# Core.net
KiCad netlist of a schematic drawn in Altium Designer
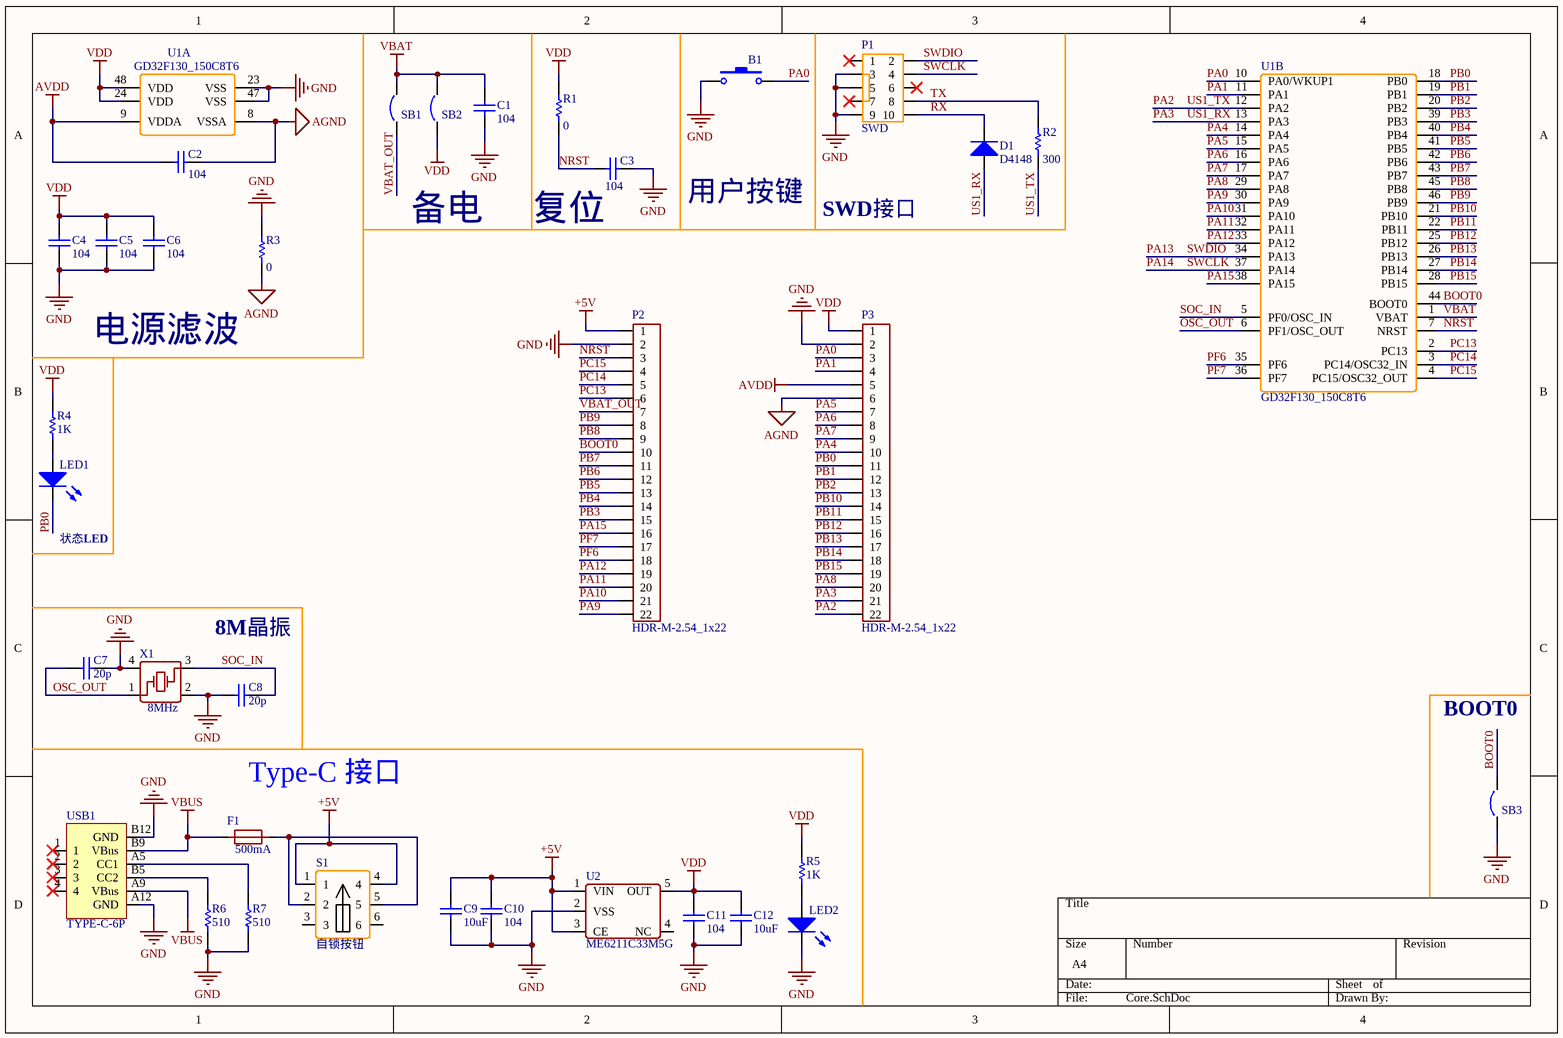
[diagram p0: Core.SchDoc]

(export (version "E")
  (design (tool "Eeschema 10.0.6"))
  (components
    (comp (ref "B1")
      (value "Button")
      (footprint "SW-SMD_L6.0-W3.5-LS8.0")
      (description "轻触按钮 - Switch")
      (fields (field (name "PUBLISHER") "Altium Limited"))
      (libsource (lib "ZSF-90") (part "Button"))
    )
    (comp (ref "C1")
      (value "104")
      (footprint "C0402")
      (description "无极性电容")
      (fields (field (name "Comment") "Cap") (field (name "PUBLISHER") "信念D力量"))
      (libsource (lib "ZSF-90") (part "Cap"))
    )
    (comp (ref "C2")
      (value "104")
      (footprint "C0402")
      (description "无极性电容")
      (fields (field (name "Comment") "Cap") (field (name "PUBLISHER") "信念D力量"))
      (libsource (lib "ZSF-90") (part "Cap"))
    )
    (comp (ref "C3")
      (value "104")
      (footprint "C0402")
      (description "无极性电容")
      (fields (field (name "Comment") "Cap") (field (name "PUBLISHER") "信念D力量"))
      (libsource (lib "ZSF-90") (part "Cap"))
    )
    (comp (ref "C4")
      (value "104")
      (footprint "C0402")
      (description "无极性电容")
      (fields (field (name "Comment") "Cap") (field (name "PUBLISHER") "信念D力量"))
      (libsource (lib "ZSF-90") (part "Cap"))
    )
    (comp (ref "C5")
      (value "104")
      (footprint "C0402")
      (description "无极性电容")
      (fields (field (name "Comment") "Cap") (field (name "PUBLISHER") "信念D力量"))
      (libsource (lib "ZSF-90") (part "Cap"))
    )
    (comp (ref "C6")
      (value "104")
      (footprint "C0402")
      (description "无极性电容")
      (fields (field (name "Comment") "Cap") (field (name "PUBLISHER") "信念D力量"))
      (libsource (lib "ZSF-90") (part "Cap"))
    )
    (comp (ref "C7")
      (value "20p")
      (footprint "C0603")
      (description "无极性电容")
      (fields (field (name "Comment") "Cap") (field (name "PUBLISHER") "信念D力量"))
      (libsource (lib "ZSF-90") (part "Cap"))
    )
    (comp (ref "C8")
      (value "20p")
      (footprint "C0603")
      (description "无极性电容")
      (fields (field (name "Comment") "Cap") (field (name "PUBLISHER") "信念D力量"))
      (libsource (lib "ZSF-90") (part "Cap"))
    )
    (comp (ref "C9")
      (value "10uF")
      (footprint "C0603")
      (description "无极性电容")
      (fields (field (name "Comment") "Cap") (field (name "PUBLISHER") "信念D力量"))
      (libsource (lib "ZSF-90") (part "Cap"))
    )
    (comp (ref "C10")
      (value "104")
      (footprint "C0402")
      (description "无极性电容")
      (fields (field (name "Comment") "Cap") (field (name "PUBLISHER") "信念D力量"))
      (libsource (lib "ZSF-90") (part "Cap"))
    )
    (comp (ref "C11")
      (value "104")
      (footprint "C0402")
      (description "无极性电容")
      (fields (field (name "Comment") "Cap") (field (name "PUBLISHER") "信念D力量"))
      (libsource (lib "ZSF-90") (part "Cap"))
    )
    (comp (ref "C12")
      (value "10uF")
      (footprint "C0603")
      (description "无极性电容")
      (fields (field (name "Comment") "Cap") (field (name "PUBLISHER") "信念D力量"))
      (libsource (lib "ZSF-90") (part "Cap"))
    )
    (comp (ref "D1")
      (value "D4148")
      (footprint "SOD-80_L3.5-W1.5-RD")
      (description "4148二极管")
      (libsource (lib "ZSF-90") (part "D4148"))
    )
    (comp (ref "F1")
      (value "500mA")
      (footprint "F0603")
      (description "保险丝 - Fuse")
      (libsource (lib "ZSF-90") (part "Fuse 1"))
    )
    (comp (ref "LED1")
      (value "LED")
      (footprint "LED0603_RED")
      (description "发光二极管")
      (libsource (lib "ZSF-90") (part "LED"))
    )
    (comp (ref "LED2")
      (value "LED")
      (footprint "LED0603_RED")
      (description "发光二极管")
      (libsource (lib "ZSF-90") (part "LED"))
    )
    (comp (ref "P1")
      (value "SWD")
      (footprint "IDC-SMD-10P-1.27MM")
      (description "牛角座")
      (libsource (lib "ZSF-90") (part "IDC-2x5"))
    )
    (comp (ref "P2")
      (value "HDR-M-2.54_1x22")
      (footprint "HDR1X22-MALE")
      (description "排针，2.54MM")
      (libsource (lib "ZSF-90") (part "HDR-M-2.54_1x22"))
    )
    (comp (ref "P3")
      (value "HDR-M-2.54_1x22")
      (footprint "HDR1X22-MALE")
      (description "排针，2.54MM")
      (libsource (lib "ZSF-90") (part "HDR-M-2.54_1x22"))
    )
    (comp (ref "R1")
      (value "0")
      (footprint "R0402")
      (description "美国电阻符号")
      (fields (field (name "Comment") "Res") (field (name "PUBLISHER") "Altium Limited"))
      (libsource (lib "ZSF-90") (part "Res"))
    )
    (comp (ref "R2")
      (value "300")
      (footprint "R0402")
      (description "美国电阻符号")
      (fields (field (name "Comment") "Res") (field (name "PUBLISHER") "Altium Limited"))
      (libsource (lib "ZSF-90") (part "Res"))
    )
    (comp (ref "R3")
      (value "0")
      (footprint "R0402")
      (description "美国电阻符号")
      (fields (field (name "Comment") "Res") (field (name "PUBLISHER") "Altium Limited"))
      (libsource (lib "ZSF-90") (part "Res"))
    )
    (comp (ref "R4")
      (value "1K")
      (footprint "R0402")
      (description "美国电阻符号")
      (fields (field (name "Comment") "Res") (field (name "PUBLISHER") "Altium Limited"))
      (libsource (lib "ZSF-90") (part "Res"))
    )
    (comp (ref "R5")
      (value "1K")
      (footprint "R0402")
      (description "美国电阻符号")
      (fields (field (name "Comment") "Res") (field (name "PUBLISHER") "Altium Limited"))
      (libsource (lib "ZSF-90") (part "Res"))
    )
    (comp (ref "R6")
      (value "510")
      (footprint "R0402")
      (description "美国电阻符号")
      (fields (field (name "Comment") "Res") (field (name "PUBLISHER") "Altium Limited"))
      (libsource (lib "ZSF-90") (part "Res"))
    )
    (comp (ref "R7")
      (value "510")
      (footprint "R0402")
      (description "美国电阻符号")
      (fields (field (name "Comment") "Res") (field (name "PUBLISHER") "Altium Limited"))
      (libsource (lib "ZSF-90") (part "Res"))
    )
    (comp (ref "S1")
      (value "自锁按钮")
      (footprint "SW-TH_5.8ZSGT")
      (description "自锁按钮开个")
      (libsource (lib "ZSF90_Connector") (part "自锁按钮"))
    )
    (comp (ref "SB1")
      (value "Circuit Breaker")
      (footprint "JP2_SMD")
      (description "断路器 短路选择 - Circuit Breaker")
      (fields (field (name "PUBLISHER") "Altium Limited"))
      (libsource (lib "ZSF-90") (part "Circuit Breaker"))
    )
    (comp (ref "SB2")
      (value "Circuit Breaker")
      (footprint "JP2_SMD")
      (description "断路器 短路选择 - Circuit Breaker")
      (fields (field (name "PUBLISHER") "Altium Limited"))
      (libsource (lib "ZSF-90") (part "Circuit Breaker"))
    )
    (comp (ref "SB3")
      (value "Circuit Breaker")
      (footprint "JP2_SMD")
      (description "断路器 短路选择 - Circuit Breaker")
      (fields (field (name "PUBLISHER") "Altium Limited"))
      (libsource (lib "ZSF-90") (part "Circuit Breaker"))
    )
    (comp (ref "U1")
      (value "GD32F130_150C8T6")
      (footprint "LQFP48 7X7")
      (description "GD32 单片机")
      (libsource (lib "ZSF-90") (part "GD32F130_150C8T6"))
    )
    (comp (ref "U2")
      (value "ME6211C33M5G")
      (footprint "SOT-23-5L")
      (description "3.3V LDO 线性稳压，带使能控制")
      (libsource (lib "ZSF-90") (part "ME6211C33M5G"))
    )
    (comp (ref "USB1")
      (value "TYPE-C-6P")
      (footprint "USB-C-SMD_6P")
      (description "Type-C USB，6P")
      (libsource (lib "ZSF-90") (part "TYPE-C-6P"))
    )
    (comp (ref "X1")
      (value "8MHz")
      (footprint "SMD-5032")
      (description "4脚晶振")
      (libsource (lib "ZSF-90") (part "XTAL-4"))
    )
  )
  (nets
    (net (code "1") (name "+5V") (class "Default")
      (node (ref "C10") (pin "2") (pinfunction "2_2") (pintype "passive"))
      (node (ref "C9") (pin "2") (pinfunction "2_2") (pintype "passive"))
      (node (ref "P2") (pin "1") (pinfunction "1_1") (pintype "passive"))
      (node (ref "S1") (pin "1") (pinfunction "1_1") (pintype "passive"))
      (node (ref "S1") (pin "4") (pinfunction "4_4") (pintype "passive"))
      (node (ref "U2") (pin "1") (pinfunction "VIN_1") (pintype "passive"))
      (node (ref "U2") (pin "3") (pinfunction "CE_3") (pintype "passive"))
    )
    (net (code "2") (name "/BOOT0") (class "Default")
      (node (ref "P2") (pin "10") (pinfunction "10_10") (pintype "passive"))
      (node (ref "SB3") (pin "2") (pinfunction "2_2") (pintype "passive"))
      (node (ref "U1") (pin "44") (pinfunction "BOOT0_44") (pintype "passive"))
    )
    (net (code "3") (name "/NRST") (class "Default")
      (node (ref "C3") (pin "2") (pinfunction "2_2") (pintype "passive"))
      (node (ref "P2") (pin "3") (pinfunction "3_3") (pintype "passive"))
      (node (ref "R1") (pin "1") (pinfunction "1_1") (pintype "passive"))
      (node (ref "U1") (pin "7") (pinfunction "NRST_7") (pintype "passive"))
    )
    (net (code "4") (name "/OSC_OUT") (class "Default")
      (node (ref "C7") (pin "2") (pinfunction "2_2") (pintype "passive"))
      (node (ref "U1") (pin "6") (pinfunction "PF1/OSC_OUT_6") (pintype "passive"))
      (node (ref "X1") (pin "1") (pinfunction "OSC1_1") (pintype "passive"))
    )
    (net (code "5") (name "/PA0") (class "Default")
      (node (ref "B1") (pin "2") (pinfunction "2_2") (pintype "passive"))
      (node (ref "P3") (pin "3") (pinfunction "3_3") (pintype "passive"))
      (node (ref "U1") (pin "10") (pinfunction "PA0/WKUP1_10") (pintype "passive"))
    )
    (net (code "6") (name "/PA1") (class "Default")
      (node (ref "P3") (pin "4") (pinfunction "4_4") (pintype "passive"))
      (node (ref "U1") (pin "11") (pinfunction "PA1_11") (pintype "passive"))
    )
    (net (code "7") (name "/PA2") (class "Default")
      (node (ref "P3") (pin "22") (pinfunction "22_22") (pintype "passive"))
      (node (ref "R2") (pin "1") (pinfunction "1_1") (pintype "passive"))
      (node (ref "U1") (pin "12") (pinfunction "PA2_12") (pintype "passive"))
    )
    (net (code "8") (name "/PA3") (class "Default")
      (node (ref "D1") (pin "2") (pinfunction "A_2") (pintype "passive"))
      (node (ref "P3") (pin "21") (pinfunction "21_21") (pintype "passive"))
      (node (ref "U1") (pin "13") (pinfunction "PA3_13") (pintype "passive"))
    )
    (net (code "9") (name "/PA4") (class "Default")
      (node (ref "P3") (pin "10") (pinfunction "10_10") (pintype "passive"))
      (node (ref "U1") (pin "14") (pinfunction "PA4_14") (pintype "passive"))
    )
    (net (code "10") (name "/PA5") (class "Default")
      (node (ref "P3") (pin "7") (pinfunction "7_7") (pintype "passive"))
      (node (ref "U1") (pin "15") (pinfunction "PA5_15") (pintype "passive"))
    )
    (net (code "11") (name "/PA6") (class "Default")
      (node (ref "P3") (pin "8") (pinfunction "8_8") (pintype "passive"))
      (node (ref "U1") (pin "16") (pinfunction "PA6_16") (pintype "passive"))
    )
    (net (code "12") (name "/PA7") (class "Default")
      (node (ref "P3") (pin "9") (pinfunction "9_9") (pintype "passive"))
      (node (ref "U1") (pin "17") (pinfunction "PA7_17") (pintype "passive"))
    )
    (net (code "13") (name "/PA8") (class "Default")
      (node (ref "P3") (pin "20") (pinfunction "20_20") (pintype "passive"))
      (node (ref "U1") (pin "29") (pinfunction "PA8_29") (pintype "passive"))
    )
    (net (code "14") (name "/PA9") (class "Default")
      (node (ref "P2") (pin "22") (pinfunction "22_22") (pintype "passive"))
      (node (ref "U1") (pin "30") (pinfunction "PA9_30") (pintype "passive"))
    )
    (net (code "15") (name "/PA10") (class "Default")
      (node (ref "P2") (pin "21") (pinfunction "21_21") (pintype "passive"))
      (node (ref "U1") (pin "31") (pinfunction "PA10_31") (pintype "passive"))
    )
    (net (code "16") (name "/PA11") (class "Default")
      (node (ref "P2") (pin "20") (pinfunction "20_20") (pintype "passive"))
      (node (ref "U1") (pin "32") (pinfunction "PA11_32") (pintype "passive"))
    )
    (net (code "17") (name "/PA12") (class "Default")
      (node (ref "P2") (pin "19") (pinfunction "19_19") (pintype "passive"))
      (node (ref "U1") (pin "33") (pinfunction "PA12_33") (pintype "passive"))
    )
    (net (code "18") (name "/PA13") (class "Default")
      (node (ref "P1") (pin "2") (pinfunction "2_2") (pintype "passive"))
      (node (ref "U1") (pin "34") (pinfunction "PA13_34") (pintype "passive"))
    )
    (net (code "19") (name "/PA14") (class "Default")
      (node (ref "P1") (pin "4") (pinfunction "4_4") (pintype "passive"))
      (node (ref "U1") (pin "37") (pinfunction "PA14_37") (pintype "passive"))
    )
    (net (code "20") (name "/PA15") (class "Default")
      (node (ref "P2") (pin "16") (pinfunction "16_16") (pintype "passive"))
      (node (ref "U1") (pin "38") (pinfunction "PA15_38") (pintype "passive"))
    )
    (net (code "21") (name "/PB0") (class "Default")
      (node (ref "LED1") (pin "2") (pinfunction "K_2") (pintype "passive"))
      (node (ref "P3") (pin "11") (pinfunction "11_11") (pintype "passive"))
      (node (ref "U1") (pin "18") (pinfunction "PB0_18") (pintype "passive"))
    )
    (net (code "22") (name "/PB1") (class "Default")
      (node (ref "P3") (pin "12") (pinfunction "12_12") (pintype "passive"))
      (node (ref "U1") (pin "19") (pinfunction "PB1_19") (pintype "passive"))
    )
    (net (code "23") (name "/PB2") (class "Default")
      (node (ref "P3") (pin "13") (pinfunction "13_13") (pintype "passive"))
      (node (ref "U1") (pin "20") (pinfunction "PB2_20") (pintype "passive"))
    )
    (net (code "24") (name "/PB3") (class "Default")
      (node (ref "P2") (pin "15") (pinfunction "15_15") (pintype "passive"))
      (node (ref "U1") (pin "39") (pinfunction "PB3_39") (pintype "passive"))
    )
    (net (code "25") (name "/PB4") (class "Default")
      (node (ref "P2") (pin "14") (pinfunction "14_14") (pintype "passive"))
      (node (ref "U1") (pin "40") (pinfunction "PB4_40") (pintype "passive"))
    )
    (net (code "26") (name "/PB5") (class "Default")
      (node (ref "P2") (pin "13") (pinfunction "13_13") (pintype "passive"))
      (node (ref "U1") (pin "41") (pinfunction "PB5_41") (pintype "passive"))
    )
    (net (code "27") (name "/PB6") (class "Default")
      (node (ref "P2") (pin "12") (pinfunction "12_12") (pintype "passive"))
      (node (ref "U1") (pin "42") (pinfunction "PB6_42") (pintype "passive"))
    )
    (net (code "28") (name "/PB7") (class "Default")
      (node (ref "P2") (pin "11") (pinfunction "11_11") (pintype "passive"))
      (node (ref "U1") (pin "43") (pinfunction "PB7_43") (pintype "passive"))
    )
    (net (code "29") (name "/PB8") (class "Default")
      (node (ref "P2") (pin "9") (pinfunction "9_9") (pintype "passive"))
      (node (ref "U1") (pin "45") (pinfunction "PB8_45") (pintype "passive"))
    )
    (net (code "30") (name "/PB9") (class "Default")
      (node (ref "P2") (pin "8") (pinfunction "8_8") (pintype "passive"))
      (node (ref "U1") (pin "46") (pinfunction "PB9_46") (pintype "passive"))
    )
    (net (code "31") (name "/PB10") (class "Default")
      (node (ref "P3") (pin "14") (pinfunction "14_14") (pintype "passive"))
      (node (ref "U1") (pin "21") (pinfunction "PB10_21") (pintype "passive"))
    )
    (net (code "32") (name "/PB11") (class "Default")
      (node (ref "P3") (pin "15") (pinfunction "15_15") (pintype "passive"))
      (node (ref "U1") (pin "22") (pinfunction "PB11_22") (pintype "passive"))
    )
    (net (code "33") (name "/PB12") (class "Default")
      (node (ref "P3") (pin "16") (pinfunction "16_16") (pintype "passive"))
      (node (ref "U1") (pin "25") (pinfunction "PB12_25") (pintype "passive"))
    )
    (net (code "34") (name "/PB13") (class "Default")
      (node (ref "P3") (pin "17") (pinfunction "17_17") (pintype "passive"))
      (node (ref "U1") (pin "26") (pinfunction "PB13_26") (pintype "passive"))
    )
    (net (code "35") (name "/PB14") (class "Default")
      (node (ref "P3") (pin "18") (pinfunction "18_18") (pintype "passive"))
      (node (ref "U1") (pin "27") (pinfunction "PB14_27") (pintype "passive"))
    )
    (net (code "36") (name "/PB15") (class "Default")
      (node (ref "P3") (pin "19") (pinfunction "19_19") (pintype "passive"))
      (node (ref "U1") (pin "28") (pinfunction "PB15_28") (pintype "passive"))
    )
    (net (code "37") (name "/PC13") (class "Default")
      (node (ref "P2") (pin "6") (pinfunction "6_6") (pintype "passive"))
      (node (ref "U1") (pin "2") (pinfunction "PC13_2") (pintype "passive"))
    )
    (net (code "38") (name "/PC14") (class "Default")
      (node (ref "P2") (pin "5") (pinfunction "5_5") (pintype "passive"))
      (node (ref "U1") (pin "3") (pinfunction "PC14/OSC32_IN_3") (pintype "passive"))
    )
    (net (code "39") (name "/PC15") (class "Default")
      (node (ref "P2") (pin "4") (pinfunction "4_4") (pintype "passive"))
      (node (ref "U1") (pin "4") (pinfunction "PC15/OSC32_OUT_4") (pintype "passive"))
    )
    (net (code "40") (name "/PF6") (class "Default")
      (node (ref "P2") (pin "18") (pinfunction "18_18") (pintype "passive"))
      (node (ref "U1") (pin "35") (pinfunction "PF6_35") (pintype "passive"))
    )
    (net (code "41") (name "/PF7") (class "Default")
      (node (ref "P2") (pin "17") (pinfunction "17_17") (pintype "passive"))
      (node (ref "U1") (pin "36") (pinfunction "PF7_36") (pintype "passive"))
    )
    (net (code "42") (name "/RX") (class "Default")
      (node (ref "D1") (pin "1") (pinfunction "K_1") (pintype "passive"))
      (node (ref "P1") (pin "10") (pinfunction "10_10") (pintype "passive"))
    )
    (net (code "43") (name "/SOC_IN") (class "Default")
      (node (ref "C8") (pin "1") (pinfunction "1_1") (pintype "passive"))
      (node (ref "U1") (pin "5") (pinfunction "PF0/OSC_IN_5") (pintype "passive"))
      (node (ref "X1") (pin "3") (pinfunction "OSC2_3") (pintype "passive"))
    )
    (net (code "44") (name "/TX") (class "Default")
      (node (ref "P1") (pin "8") (pinfunction "8_8") (pintype "passive"))
      (node (ref "R2") (pin "2") (pinfunction "2_2") (pintype "passive"))
    )
    (net (code "45") (name "/VBAT_OUT") (class "Default")
      (node (ref "P2") (pin "7") (pinfunction "7_7") (pintype "passive"))
      (node (ref "SB1") (pin "1") (pinfunction "1_1") (pintype "passive"))
    )
    (net (code "46") (name "AGND") (class "Default")
      (node (ref "C2") (pin "2") (pinfunction "2_2") (pintype "passive"))
      (node (ref "P3") (pin "6") (pinfunction "6_6") (pintype "passive"))
      (node (ref "R3") (pin "1") (pinfunction "1_1") (pintype "passive"))
      (node (ref "U1") (pin "8") (pinfunction "VSSA_8") (pintype "passive"))
    )
    (net (code "47") (name "AVDD") (class "Default")
      (node (ref "C2") (pin "1") (pinfunction "1_1") (pintype "passive"))
      (node (ref "P3") (pin "5") (pinfunction "5_5") (pintype "passive"))
      (node (ref "U1") (pin "9") (pinfunction "VDDA_9") (pintype "passive"))
    )
    (net (code "48") (name "GND") (class "Default")
      (node (ref "B1") (pin "1") (pinfunction "1_1") (pintype "passive"))
      (node (ref "C1") (pin "1") (pinfunction "1_1") (pintype "passive"))
      (node (ref "C10") (pin "1") (pinfunction "1_1") (pintype "passive"))
      (node (ref "C11") (pin "1") (pinfunction "1_1") (pintype "passive"))
      (node (ref "C12") (pin "1") (pinfunction "1_1") (pintype "passive"))
      (node (ref "C3") (pin "1") (pinfunction "1_1") (pintype "passive"))
      (node (ref "C4") (pin "1") (pinfunction "1_1") (pintype "passive"))
      (node (ref "C5") (pin "1") (pinfunction "1_1") (pintype "passive"))
      (node (ref "C6") (pin "1") (pinfunction "1_1") (pintype "passive"))
      (node (ref "C7") (pin "1") (pinfunction "1_1") (pintype "passive"))
      (node (ref "C8") (pin "2") (pinfunction "2_2") (pintype "passive"))
      (node (ref "C9") (pin "1") (pinfunction "1_1") (pintype "passive"))
      (node (ref "LED2") (pin "2") (pinfunction "K_2") (pintype "passive"))
      (node (ref "P1") (pin "3") (pinfunction "3_3") (pintype "passive"))
      (node (ref "P1") (pin "5") (pinfunction "5_5") (pintype "passive"))
      (node (ref "P1") (pin "9") (pinfunction "9_9") (pintype "passive"))
      (node (ref "P2") (pin "2") (pinfunction "2_2") (pintype "passive"))
      (node (ref "P3") (pin "2") (pinfunction "2_2") (pintype "passive"))
      (node (ref "R3") (pin "2") (pinfunction "2_2") (pintype "passive"))
      (node (ref "R6") (pin "2") (pinfunction "2_2") (pintype "passive"))
      (node (ref "R7") (pin "2") (pinfunction "2_2") (pintype "passive"))
      (node (ref "SB3") (pin "1") (pinfunction "1_1") (pintype "passive"))
      (node (ref "U1") (pin "23") (pinfunction "VSS_23") (pintype "passive"))
      (node (ref "U1") (pin "47") (pinfunction "VSS_47") (pintype "passive"))
      (node (ref "U2") (pin "2") (pinfunction "VSS_2") (pintype "passive"))
      (node (ref "USB1") (pin "A12") (pinfunction "GND_A12") (pintype "passive"))
      (node (ref "USB1") (pin "B12") (pinfunction "GND_B12") (pintype "passive"))
      (node (ref "X1") (pin "2") (pinfunction "2_2") (pintype "passive"))
      (node (ref "X1") (pin "4") (pinfunction "4_4") (pintype "passive"))
    )
    (net (code "49") (name "Net-(F1-Pad2)") (class "Default")
      (node (ref "F1") (pin "2") (pinfunction "2_2") (pintype "passive"))
      (node (ref "S1") (pin "2") (pinfunction "2_2") (pintype "passive"))
      (node (ref "S1") (pin "5") (pinfunction "5_5") (pintype "passive"))
    )
    (net (code "50") (name "Net-(LED1-A)") (class "Default")
      (node (ref "LED1") (pin "1") (pinfunction "A_1") (pintype "passive"))
      (node (ref "R4") (pin "1") (pinfunction "1_1") (pintype "passive"))
    )
    (net (code "51") (name "Net-(LED2-A)") (class "Default")
      (node (ref "LED2") (pin "1") (pinfunction "A_1") (pintype "passive"))
      (node (ref "R5") (pin "1") (pinfunction "1_1") (pintype "passive"))
    )
    (net (code "52") (name "Net-(USB1-CC1)") (class "Default")
      (node (ref "R7") (pin "1") (pinfunction "1_1") (pintype "passive"))
      (node (ref "USB1") (pin "A5") (pinfunction "CC1_A5") (pintype "passive"))
    )
    (net (code "53") (name "Net-(USB1-CC2)") (class "Default")
      (node (ref "R6") (pin "1") (pinfunction "1_1") (pintype "passive"))
      (node (ref "USB1") (pin "B5") (pinfunction "CC2_B5") (pintype "passive"))
    )
    (net (code "54") (name "VBAT") (class "Default")
      (node (ref "C1") (pin "2") (pinfunction "2_2") (pintype "passive"))
      (node (ref "SB1") (pin "2") (pinfunction "2_2") (pintype "passive"))
      (node (ref "SB2") (pin "2") (pinfunction "2_2") (pintype "passive"))
      (node (ref "U1") (pin "1") (pinfunction "VBAT_1") (pintype "passive"))
    )
    (net (code "55") (name "VBUS") (class "Default")
      (node (ref "F1") (pin "1") (pinfunction "1_1") (pintype "passive"))
      (node (ref "USB1") (pin "A9") (pinfunction "VBus_A9") (pintype "passive"))
      (node (ref "USB1") (pin "B9") (pinfunction "VBus_B9") (pintype "passive"))
    )
    (net (code "56") (name "VDD") (class "Default")
      (node (ref "C11") (pin "2") (pinfunction "2_2") (pintype "passive"))
      (node (ref "C12") (pin "2") (pinfunction "2_2") (pintype "passive"))
      (node (ref "C4") (pin "2") (pinfunction "2_2") (pintype "passive"))
      (node (ref "C5") (pin "2") (pinfunction "2_2") (pintype "passive"))
      (node (ref "C6") (pin "2") (pinfunction "2_2") (pintype "passive"))
      (node (ref "P3") (pin "1") (pinfunction "1_1") (pintype "passive"))
      (node (ref "R1") (pin "2") (pinfunction "2_2") (pintype "passive"))
      (node (ref "R4") (pin "2") (pinfunction "2_2") (pintype "passive"))
      (node (ref "R5") (pin "2") (pinfunction "2_2") (pintype "passive"))
      (node (ref "SB2") (pin "1") (pinfunction "1_1") (pintype "passive"))
      (node (ref "U1") (pin "24") (pinfunction "VDD_24") (pintype "passive"))
      (node (ref "U1") (pin "48") (pinfunction "VDD_48") (pintype "passive"))
      (node (ref "U2") (pin "5") (pinfunction "OUT_5") (pintype "passive"))
    )
    (net (code "57") (name "unconnected-(P1-Pad1)") (class "Default")
      (node (ref "P1") (pin "1") (pinfunction "1_1") (pintype "passive+no_connect"))
    )
    (net (code "58") (name "unconnected-(P1-Pad6)") (class "Default")
      (node (ref "P1") (pin "6") (pinfunction "6_6") (pintype "passive+no_connect"))
    )
    (net (code "59") (name "unconnected-(P1-Pad7)") (class "Default")
      (node (ref "P1") (pin "7") (pinfunction "7_7") (pintype "passive+no_connect"))
    )
    (net (code "60") (name "unconnected-(S1-Pad3)") (class "Default")
      (node (ref "S1") (pin "3") (pinfunction "3_3") (pintype "passive"))
    )
    (net (code "61") (name "unconnected-(S1-Pad6)") (class "Default")
      (node (ref "S1") (pin "6") (pinfunction "6_6") (pintype "passive"))
    )
    (net (code "62") (name "unconnected-(U2-NC-Pad4)") (class "Default")
      (node (ref "U2") (pin "4") (pinfunction "NC_4") (pintype "passive"))
    )
    (net (code "63") (name "unconnected-(USB1-Pad1)") (class "Default")
      (node (ref "USB1") (pin "1") (pinfunction "1_1") (pintype "passive+no_connect"))
    )
    (net (code "64") (name "unconnected-(USB1-Pad2)") (class "Default")
      (node (ref "USB1") (pin "2") (pinfunction "2_2") (pintype "passive+no_connect"))
    )
    (net (code "65") (name "unconnected-(USB1-Pad3)") (class "Default")
      (node (ref "USB1") (pin "3") (pinfunction "3_3") (pintype "passive+no_connect"))
    )
    (net (code "66") (name "unconnected-(USB1-Pad4)") (class "Default")
      (node (ref "USB1") (pin "4") (pinfunction "4_4") (pintype "passive+no_connect"))
    )
  )
)
